# Sheet_1_2023-04-29.net
KiCad netlist of a schematic drawn in Altium Designer
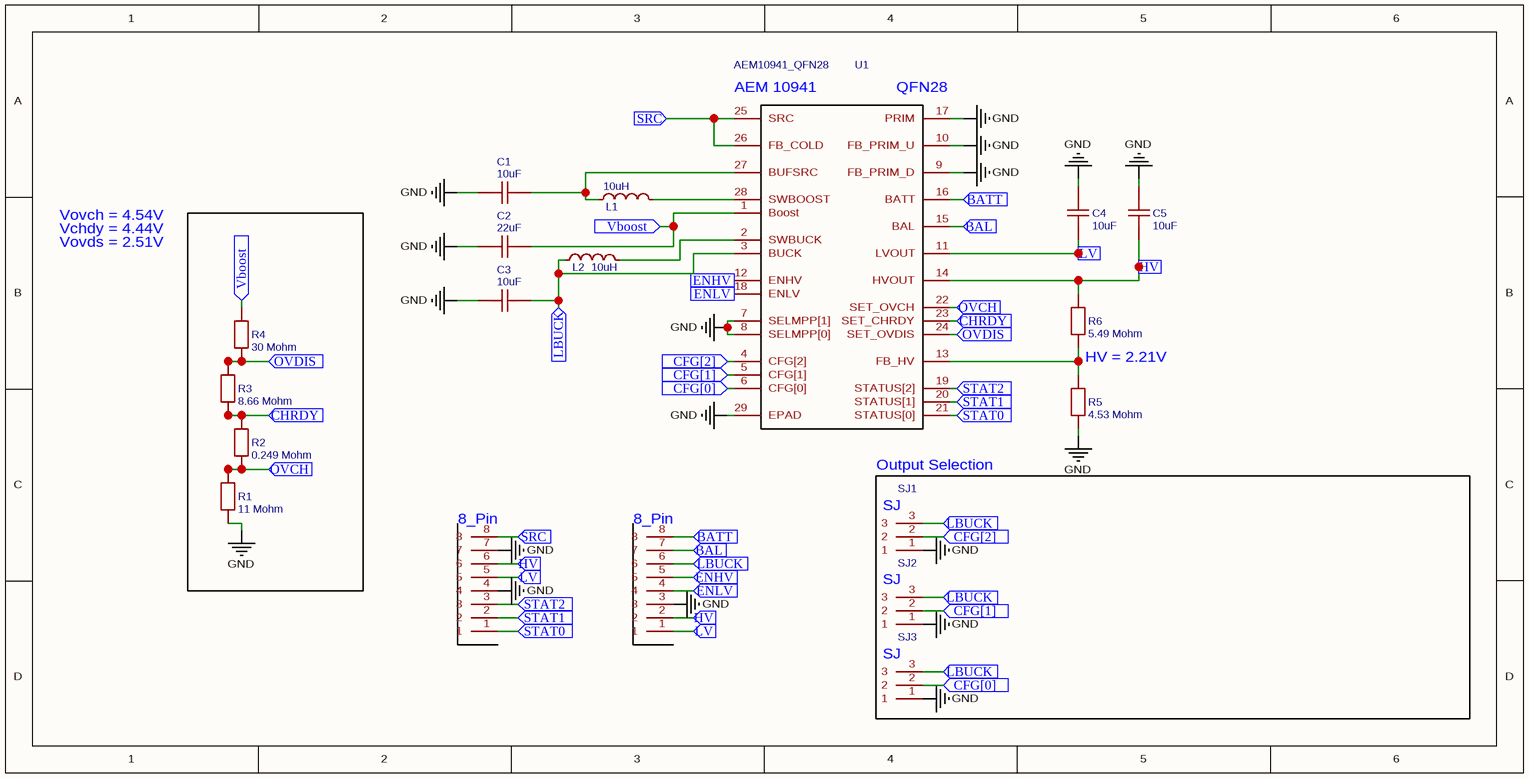
[diagram p0: Sheet_1_2023-04-29.schdoc]

(export (version "E")
  (design (tool "Eeschema 10.0.6"))
  (components
    (comp (ref "C1")
      (value "10uF")
      (fields (field (name "CONTRIBUTOR") "LCEDA_Lib"))
      (libsource (lib "altium-import") (part "root_0_10uF_"))
    )
    (comp (ref "C2")
      (value "22uF")
      (fields (field (name "CONTRIBUTOR") "LCEDA_Lib"))
      (libsource (lib "altium-import") (part "root_0_22uF_"))
    )
    (comp (ref "C3")
      (value "10uF")
      (fields (field (name "CONTRIBUTOR") "LCEDA_Lib"))
      (libsource (lib "altium-import") (part "root_0_10uF_"))
    )
    (comp (ref "C4")
      (value "10uF")
      (fields (field (name "CONTRIBUTOR") "LCEDA_Lib"))
      (libsource (lib "altium-import") (part "root_3_10uF_"))
    )
    (comp (ref "C5")
      (value "10uF")
      (fields (field (name "CONTRIBUTOR") "LCEDA_Lib"))
      (libsource (lib "altium-import") (part "root_3_10uF_"))
    )
    (comp (ref "L1")
      (value "LPS4012")
      (fields
        (field (name "BOM_MANUFACTURER PART") "LPS4012-103MRB")
        (field (name "CONTRIBUTOR") "Bastien Politi")
      )
      (libsource (lib "altium-import") (part "root_0_LPS4012_"))
    )
    (comp (ref "L2")
      (value "10uH")
      (fields
        (field (name "BOM_MANUFACTURER PART") "MLZ1608M100WT000")
        (field (name "BOM_SUPPLIER PART") "C76798")
      )
      (libsource (lib "altium-import") (part "root_0_10uH_"))
    )
    (comp (ref "R1")
      (value "11 Mohm")
      (fields (field (name "CONTRIBUTOR") "LCEDA_Lib"))
      (libsource (lib "altium-import") (part "root_1_11 Mohm_"))
    )
    (comp (ref "R2")
      (value "0.249 Mohm")
      (fields (field (name "CONTRIBUTOR") "LCEDA_Lib"))
      (libsource (lib "altium-import") (part "root_1_0.249 Mohm_"))
    )
    (comp (ref "R3")
      (value "8.66 Mohm")
      (fields (field (name "CONTRIBUTOR") "LCEDA_Lib"))
      (libsource (lib "altium-import") (part "root_1_8.66 Mohm_"))
    )
    (comp (ref "R4")
      (value "30 Mohm")
      (fields (field (name "CONTRIBUTOR") "LCEDA_Lib"))
      (libsource (lib "altium-import") (part "root_1_30 Mohm_"))
    )
    (comp (ref "R5")
      (value "4.53 Mohm")
      (fields (field (name "CONTRIBUTOR") "LCEDA_Lib"))
      (libsource (lib "altium-import") (part "root_1_4.53 Mohm_"))
    )
    (comp (ref "R6")
      (value "5.49 Mohm")
      (fields (field (name "CONTRIBUTOR") "LCEDA_Lib"))
      (libsource (lib "altium-import") (part "root_1_5.49 Mohm_"))
    )
    (comp (ref "SJ1")
      (value "Solder_Jumper")
      (fields (field (name "CONTRIBUTOR") "madub43"))
      (libsource (lib "altium-import") (part "root_0_Solder_Jumper_"))
    )
    (comp (ref "SJ2")
      (value "Solder_Jumper")
      (fields (field (name "CONTRIBUTOR") "madub43"))
      (libsource (lib "altium-import") (part "root_0_Solder_Jumper_"))
    )
    (comp (ref "SJ3")
      (value "Solder_Jumper")
      (fields (field (name "CONTRIBUTOR") "madub43"))
      (libsource (lib "altium-import") (part "root_0_Solder_Jumper_"))
    )
    (comp (ref "U1")
      (value "AEM10941_QFN28")
      (fields
        (field (name "BOM_MANUFACTURER PART") "10AEM10941C0000")
        (field (name "BOM_SUPPLIER PART") "120-AEM10941-QFN")
        (field (name "CONTRIBUTOR") "madub43")
      )
      (libsource (lib "altium-import") (part "root_0_AEM10941_QFN28_"))
    )
    (comp (ref "U6")
      (value "8_pin_2.54_header")
      (fields (field (name "CONTRIBUTOR") "madub43"))
      (libsource (lib "altium-import") (part "root_0_8_pin_2.54_header_"))
    )
    (comp (ref "U7")
      (value "8_pin_2.54_header")
      (fields (field (name "CONTRIBUTOR") "madub43"))
      (libsource (lib "altium-import") (part "root_0_8_pin_2.54_header_"))
    )
  )
  (nets
    (net (code "1") (name "/BAL") (class "Default")
      (node (ref "U1") (pin "15") (pinfunction "BAL_15") (pintype "passive"))
      (node (ref "U6") (pin "7") (pinfunction "7_7") (pintype "passive"))
    )
    (net (code "2") (name "/BATT") (class "Default")
      (node (ref "U1") (pin "16") (pinfunction "BATT_16") (pintype "passive"))
      (node (ref "U6") (pin "8") (pinfunction "8_8") (pintype "passive"))
    )
    (net (code "3") (name "/CFG[0]") (class "Default")
      (node (ref "SJ3") (pin "2") (pinfunction "2_2") (pintype "passive"))
      (node (ref "U1") (pin "6") (pinfunction "CFG[0]_6") (pintype "passive"))
    )
    (net (code "4") (name "/CFG[1]") (class "Default")
      (node (ref "SJ2") (pin "2") (pinfunction "2_2") (pintype "passive"))
      (node (ref "U1") (pin "5") (pinfunction "CFG[1]_5") (pintype "passive"))
    )
    (net (code "5") (name "/CFG[2]") (class "Default")
      (node (ref "SJ1") (pin "2") (pinfunction "2_2") (pintype "passive"))
      (node (ref "U1") (pin "4") (pinfunction "CFG[2]_4") (pintype "passive"))
    )
    (net (code "6") (name "/CHRDY") (class "Default")
      (node (ref "R2") (pin "2") (pinfunction "2_2") (pintype "passive"))
      (node (ref "R3") (pin "1") (pinfunction "1_1") (pintype "passive"))
      (node (ref "U1") (pin "23") (pinfunction "SET_CHRDY_23") (pintype "passive"))
    )
    (net (code "7") (name "/ENHV") (class "Default")
      (node (ref "U1") (pin "12") (pinfunction "ENHV_12") (pintype "passive"))
      (node (ref "U6") (pin "5") (pinfunction "5_5") (pintype "passive"))
    )
    (net (code "8") (name "/ENLV") (class "Default")
      (node (ref "U1") (pin "18") (pinfunction "ENLV_18") (pintype "passive"))
      (node (ref "U6") (pin "4") (pinfunction "4_4") (pintype "passive"))
    )
    (net (code "9") (name "/HV") (class "Default")
      (node (ref "C5") (pin "2") (pinfunction "2_2") (pintype "passive"))
      (node (ref "R6") (pin "2") (pinfunction "2_2") (pintype "passive"))
      (node (ref "U1") (pin "14") (pinfunction "HVOUT_14") (pintype "passive"))
      (node (ref "U6") (pin "2") (pinfunction "2_2") (pintype "passive"))
      (node (ref "U7") (pin "6") (pinfunction "6_6") (pintype "passive"))
    )
    (net (code "10") (name "/LBUCK") (class "Default")
      (node (ref "C3") (pin "2") (pinfunction "2_2") (pintype "passive"))
      (node (ref "L2") (pin "1") (pinfunction "1_1") (pintype "passive"))
      (node (ref "SJ1") (pin "3") (pinfunction "3_3") (pintype "passive"))
      (node (ref "SJ2") (pin "3") (pinfunction "3_3") (pintype "passive"))
      (node (ref "SJ3") (pin "3") (pinfunction "3_3") (pintype "passive"))
      (node (ref "U1") (pin "3") (pinfunction "BUCK_3") (pintype "passive"))
      (node (ref "U6") (pin "6") (pinfunction "6_6") (pintype "passive"))
    )
    (net (code "11") (name "/LV") (class "Default")
      (node (ref "C4") (pin "2") (pinfunction "2_2") (pintype "passive"))
      (node (ref "U1") (pin "11") (pinfunction "LVOUT_11") (pintype "passive"))
      (node (ref "U6") (pin "1") (pinfunction "1_1") (pintype "passive"))
      (node (ref "U7") (pin "5") (pinfunction "5_5") (pintype "passive"))
    )
    (net (code "12") (name "/OVCH") (class "Default")
      (node (ref "R1") (pin "2") (pinfunction "2_2") (pintype "passive"))
      (node (ref "R2") (pin "1") (pinfunction "1_1") (pintype "passive"))
      (node (ref "U1") (pin "22") (pinfunction "SET_OVCH_22") (pintype "passive"))
    )
    (net (code "13") (name "/OVDIS") (class "Default")
      (node (ref "R3") (pin "2") (pinfunction "2_2") (pintype "passive"))
      (node (ref "R4") (pin "1") (pinfunction "1_1") (pintype "passive"))
      (node (ref "U1") (pin "24") (pinfunction "SET_OVDIS_24") (pintype "passive"))
    )
    (net (code "14") (name "/SRC") (class "Default")
      (node (ref "U1") (pin "25") (pinfunction "SRC_25") (pintype "passive"))
      (node (ref "U1") (pin "26") (pinfunction "FB_COLD_26") (pintype "passive"))
      (node (ref "U7") (pin "8") (pinfunction "8_8") (pintype "passive"))
    )
    (net (code "15") (name "/STAT0") (class "Default")
      (node (ref "U1") (pin "21") (pinfunction "STATUS[0]_21") (pintype "passive"))
      (node (ref "U7") (pin "1") (pinfunction "1_1") (pintype "passive"))
    )
    (net (code "16") (name "/STAT1") (class "Default")
      (node (ref "U1") (pin "20") (pinfunction "STATUS[1]_20") (pintype "passive"))
      (node (ref "U7") (pin "2") (pinfunction "2_2") (pintype "passive"))
    )
    (net (code "17") (name "/STAT2") (class "Default")
      (node (ref "U1") (pin "19") (pinfunction "STATUS[2]_19") (pintype "passive"))
      (node (ref "U7") (pin "3") (pinfunction "3_3") (pintype "passive"))
    )
    (net (code "18") (name "/Vboost") (class "Default")
      (node (ref "C2") (pin "2") (pinfunction "2_2") (pintype "passive"))
      (node (ref "R4") (pin "2") (pinfunction "2_2") (pintype "passive"))
      (node (ref "U1") (pin "1") (pinfunction "Boost_1") (pintype "passive"))
    )
    (net (code "19") (name "GND") (class "Default")
      (node (ref "C1") (pin "1") (pinfunction "1_1") (pintype "passive"))
      (node (ref "C2") (pin "1") (pinfunction "1_1") (pintype "passive"))
      (node (ref "C3") (pin "1") (pinfunction "1_1") (pintype "passive"))
      (node (ref "C4") (pin "1") (pinfunction "1_1") (pintype "passive"))
      (node (ref "C5") (pin "1") (pinfunction "1_1") (pintype "passive"))
      (node (ref "R1") (pin "1") (pinfunction "1_1") (pintype "passive"))
      (node (ref "R5") (pin "1") (pinfunction "1_1") (pintype "passive"))
      (node (ref "SJ1") (pin "1") (pinfunction "1_1") (pintype "passive"))
      (node (ref "SJ2") (pin "1") (pinfunction "1_1") (pintype "passive"))
      (node (ref "SJ3") (pin "1") (pinfunction "1_1") (pintype "passive"))
      (node (ref "U1") (pin "10") (pinfunction "FB_PRIM_U_10") (pintype "passive"))
      (node (ref "U1") (pin "17") (pinfunction "PRIM_17") (pintype "passive"))
      (node (ref "U1") (pin "29") (pinfunction "EPAD_29") (pintype "passive"))
      (node (ref "U1") (pin "7") (pinfunction "SELMPP[1]_7") (pintype "passive"))
      (node (ref "U1") (pin "8") (pinfunction "SELMPP[0]_8") (pintype "passive"))
      (node (ref "U1") (pin "9") (pinfunction "FB_PRIM_D_9") (pintype "passive"))
      (node (ref "U6") (pin "3") (pinfunction "3_3") (pintype "passive"))
      (node (ref "U7") (pin "4") (pinfunction "4_4") (pintype "passive"))
      (node (ref "U7") (pin "7") (pinfunction "7_7") (pintype "passive"))
    )
    (net (code "20") (name "Net-(U1-BUFSRC)") (class "Default")
      (node (ref "C1") (pin "2") (pinfunction "2_2") (pintype "passive"))
      (node (ref "L1") (pin "1") (pinfunction "1_1") (pintype "passive"))
      (node (ref "U1") (pin "27") (pinfunction "BUFSRC_27") (pintype "passive"))
    )
    (net (code "21") (name "Net-(U1-FB_HV)") (class "Default")
      (node (ref "R5") (pin "2") (pinfunction "2_2") (pintype "passive"))
      (node (ref "R6") (pin "1") (pinfunction "1_1") (pintype "passive"))
      (node (ref "U1") (pin "13") (pinfunction "FB_HV_13") (pintype "passive"))
    )
    (net (code "22") (name "Net-(U1-SWBOOST)") (class "Default")
      (node (ref "L1") (pin "2") (pinfunction "2_2") (pintype "passive"))
      (node (ref "U1") (pin "28") (pinfunction "SWBOOST_28") (pintype "passive"))
    )
    (net (code "23") (name "Net-(U1-SWBUCK)") (class "Default")
      (node (ref "L2") (pin "2") (pinfunction "2_2") (pintype "passive"))
      (node (ref "U1") (pin "2") (pinfunction "SWBUCK_2") (pintype "passive"))
    )
  )
)
